# Thermocouples.net
KiCad netlist of a schematic drawn in Altium Designer
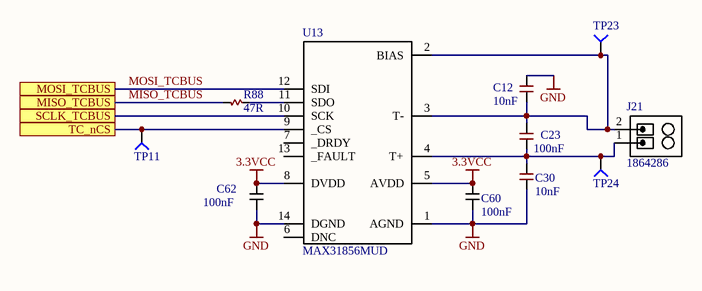
[diagram p0: Thermocouples.SchDoc]

(export (version "E")
  (design (tool "Eeschema 10.0.6"))
  (components
    (comp (ref "C12")
      (value "10nF")
      (footprint "C0402")
      (description "CAP CER 10nF 50V X7R 0402")
      (fields (field (name "TOLERANCE") "5%") (field (name "MANUFACTURER") "Murata"))
      (libsource (lib "Capacitors") (part "10nF 0402 50V X7R"))
    )
    (comp (ref "C23")
      (value "100nF")
      (footprint "C0603")
      (description "CAP CER 0603 100nF 50V 10% X7R")
      (fields (field (name "MANUFACTURER") "Kemet") (field (name "PART") "C0603C104K5RACTU"))
      (libsource (lib "Capacitors") (part "100nF 0603 50V X7R"))
    )
    (comp (ref "C30")
      (value "10nF")
      (footprint "C0402")
      (description "CAP CER 10nF 50V X7R 0402")
      (fields (field (name "TOLERANCE") "5%") (field (name "MANUFACTURER") "Murata"))
      (libsource (lib "Capacitors") (part "10nF 0402 50V X7R"))
    )
    (comp (ref "C60")
      (value "100nF")
      (footprint "C0201 Large Pads")
      (description "CAP CER 0.1UF 6.3V 10% X5R 0201")
      (fields (field (name "MANUFACTURER") "Samsung") (field (name "TOLERANCE") "10%"))
      (libsource (lib "Capacitors") (part "100nF 6.3V X5R 0201"))
    )
    (comp (ref "C62")
      (value "100nF")
      (footprint "C0201 Large Pads")
      (description "CAP CER 0.1UF 6.3V 10% X5R 0201")
      (fields (field (name "MANUFACTURER") "Samsung") (field (name "TOLERANCE") "10%"))
      (libsource (lib "Capacitors") (part "100nF 6.3V X5R 0201"))
    )
    (comp (ref "J21")
      (value "1864286")
      (footprint "1864286")
      (description "TERM BLOCK 2POS 45DEG 3.5MM PCB")
      (fields (field (name "MANUFACTURER") "Phoenix Contact") (field (name "TOLERANCE") "-NA-"))
      (libsource (lib "Connectors") (part "2POS 45DEG 3.5MM Push-Spring Terminal Block"))
    )
    (comp (ref "R88")
      (value "47R")
      (footprint "R0402")
      (description "RES 47 OHM 1% 1/16W 0402")
      (fields (field (name "MANUFACTURER") "Vishay Dale") (field (name "TOLERANCE") "+/- 1%"))
      (libsource (lib "Resistors") (part "47R 1% 0402"))
    )
    (comp (ref "TP11")
      (value "TP4")
      (footprint "TP-2")
      (description "Socket")
      (fields (field (name "PART") "NOTAPART-Testpoint"))
      (libsource (lib "Archim") (part "Socket"))
    )
    (comp (ref "TP23")
      (value "TP4")
      (footprint "TP-2")
      (description "Socket")
      (fields (field (name "PART") "NOTAPART-Testpoint"))
      (libsource (lib "Archim") (part "Socket"))
    )
    (comp (ref "TP24")
      (value "TP4")
      (footprint "TP-2")
      (description "Socket")
      (fields (field (name "PART") "NOTAPART-Testpoint"))
      (libsource (lib "Archim") (part "Socket"))
    )
    (comp (ref "U13")
      (value "MAX31856MUD")
      (footprint "TSSOP-14L 65P640X110")
      (description "IC CONV THERMOCOUPLE 14TSSOP")
      (fields (field (name "MANUFACTURER") "Maxim") (field (name "VOLTAGE") "3.3V"))
      (libsource (lib "ICs-Analog") (part "MAX31856"))
    )
  )
  (nets
    (net (code "1") (name "/MISO_TCBUS") (class "Default")
      (node (ref "R88") (pin "2") (pinfunction "2_2") (pintype "passive"))
    )
    (net (code "2") (name "/MOSI_TCBUS") (class "Default")
      (node (ref "U13") (pin "12") (pinfunction "SDI_12") (pintype "power_in"))
    )
    (net (code "3") (name "/SCLK_TCBUS") (class "Default")
      (node (ref "U13") (pin "10") (pinfunction "SCK_10") (pintype "power_in"))
    )
    (net (code "4") (name "/TC_nCS") (class "Default")
      (node (ref "TP11") (pin "1") (pinfunction "1_1") (pintype "passive"))
      (node (ref "U13") (pin "9") (pinfunction "_CS_9") (pintype "power_in"))
    )
    (net (code "5") (name "3.3VCC") (class "Default")
      (node (ref "C60") (pin "2") (pinfunction "2_2") (pintype "passive"))
      (node (ref "C62") (pin "2") (pinfunction "2_2") (pintype "passive"))
      (node (ref "U13") (pin "5") (pinfunction "AVDD_5") (pintype "passive"))
      (node (ref "U13") (pin "8") (pinfunction "DVDD_8") (pintype "passive"))
    )
    (net (code "6") (name "GND") (class "Default")
      (node (ref "C12") (pin "2") (pinfunction "2_2") (pintype "passive"))
      (node (ref "C30") (pin "1") (pinfunction "1_1") (pintype "passive"))
      (node (ref "C60") (pin "1") (pinfunction "1_1") (pintype "passive"))
      (node (ref "C62") (pin "1") (pinfunction "1_1") (pintype "passive"))
      (node (ref "U13") (pin "1") (pinfunction "AGND_1") (pintype "passive"))
      (node (ref "U13") (pin "14") (pinfunction "DGND_14") (pintype "power_in"))
    )
    (net (code "7") (name "Net-(U13-BIAS)") (class "Default")
      (node (ref "C12") (pin "1") (pinfunction "1_1") (pintype "passive"))
      (node (ref "C23") (pin "2") (pinfunction "2_2") (pintype "passive"))
      (node (ref "J21") (pin "2") (pinfunction "S_2") (pintype "passive"))
      (node (ref "TP23") (pin "1") (pinfunction "1_1") (pintype "passive"))
      (node (ref "U13") (pin "2") (pinfunction "BIAS_2") (pintype "passive"))
      (node (ref "U13") (pin "3") (pinfunction "T-_3") (pintype "passive"))
    )
    (net (code "8") (name "Net-(U13-SDO)") (class "Default")
      (node (ref "R88") (pin "1") (pinfunction "1_1") (pintype "passive"))
      (node (ref "U13") (pin "11") (pinfunction "SDO_11") (pintype "power_in"))
    )
    (net (code "9") (name "Net-(U13-T+)") (class "Default")
      (node (ref "C23") (pin "1") (pinfunction "1_1") (pintype "passive"))
      (node (ref "C30") (pin "2") (pinfunction "2_2") (pintype "passive"))
      (node (ref "J21") (pin "1") (pinfunction "S_1") (pintype "passive"))
      (node (ref "TP24") (pin "1") (pinfunction "1_1") (pintype "passive"))
      (node (ref "U13") (pin "4") (pinfunction "T+_4") (pintype "passive"))
    )
    (net (code "10") (name "unconnected-(U13-DNC-Pad6)") (class "Default")
      (node (ref "U13") (pin "6") (pinfunction "DNC_6") (pintype "passive"))
    )
    (net (code "11") (name "unconnected-(U13-_DRDY-Pad7)") (class "Default")
      (node (ref "U13") (pin "7") (pinfunction "_DRDY_7") (pintype "passive"))
    )
    (net (code "12") (name "unconnected-(U13-_FAULT-Pad13)") (class "Default")
      (node (ref "U13") (pin "13") (pinfunction "_FAULT_13") (pintype "power_in"))
    )
  )
)
